# schematic.net
KiCad netlist of a schematic drawn in EAGLE
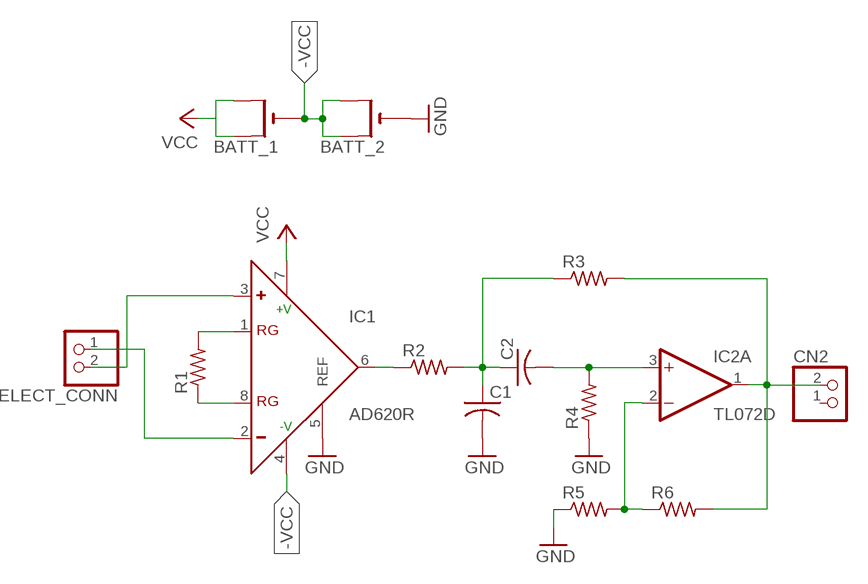
[diagram p0: schematic, sheet 1]

(export (version "E")
  (design (tool "Eeschema 10.0.6"))
  (components
    (comp (ref "BATT_1")
      (value "CR1220SMT")
      (footprint "eagle-import:CR1220-SMD")
      (libsource (lib "eagle-import") (part "CR1220SMT"))
    )
    (comp (ref "BATT_2")
      (value "CR1220SMT")
      (footprint "eagle-import:CR1220-SMD")
      (libsource (lib "eagle-import") (part "CR1220SMT"))
    )
    (comp (ref "C1")
      (value "C-USC0805")
      (footprint "eagle-import:C0805")
      (libsource (lib "eagle-import") (part "C-USC0805"))
    )
    (comp (ref "C2")
      (value "C-USC0805")
      (footprint "eagle-import:C0805")
      (libsource (lib "eagle-import") (part "C-USC0805"))
    )
    (comp (ref "CN2")
      (value "JST_2PIN-SMT-RA")
      (footprint "eagle-import:JST-PH-2-SMT-RA")
      (libsource (lib "eagle-import") (part "JST_2PIN-SMT-RA"))
    )
    (comp (ref "ELECT_CONN")
      (value "JST_2PIN-SMT-RA")
      (footprint "eagle-import:JST-PH-2-SMT-RA")
      (libsource (lib "eagle-import") (part "JST_2PIN-SMT-RA"))
    )
    (comp (ref "IC1")
      (value "AD620R")
      (footprint "eagle-import:SO8")
      (fields (field (name "MPN") "AD620AR"))
      (libsource (lib "eagle-import") (part "AD620R"))
    )
    (comp (ref "IC2")
      (value "TL072D")
      (footprint "eagle-import:SO08")
      (libsource (lib "eagle-import") (part "TL072D"))
    )
    (comp (ref "R1")
      (value "R-US_R0805")
      (footprint "eagle-import:R0805")
      (libsource (lib "eagle-import") (part "R-US_R0805"))
    )
    (comp (ref "R2")
      (value "R-US_R0805")
      (footprint "eagle-import:R0805")
      (libsource (lib "eagle-import") (part "R-US_R0805"))
    )
    (comp (ref "R3")
      (value "R-US_R0805")
      (footprint "eagle-import:R0805")
      (libsource (lib "eagle-import") (part "R-US_R0805"))
    )
    (comp (ref "R4")
      (value "R-US_R0805")
      (footprint "eagle-import:R0805")
      (libsource (lib "eagle-import") (part "R-US_R0805"))
    )
    (comp (ref "R5")
      (value "R-US_R0805")
      (footprint "eagle-import:R0805")
      (libsource (lib "eagle-import") (part "R-US_R0805"))
    )
    (comp (ref "R6")
      (value "R-US_R0805")
      (footprint "eagle-import:R0805")
      (libsource (lib "eagle-import") (part "R-US_R0805"))
    )
  )
  (nets
    (net (code "1") (name "-VCC") (class "Default")
      (node (ref "BATT_1") (pin "-") (pinfunction "-_-") (pintype "passive"))
      (node (ref "BATT_2") (pin "+$1") (pinfunction "+_+$1") (pintype "passive"))
      (node (ref "BATT_2") (pin "+$2") (pinfunction "+1_+$2") (pintype "passive"))
      (node (ref "IC1") (pin "4") (pinfunction "-V_4") (pintype "power_in"))
    )
    (net (code "2") (name "GND") (class "Default")
      (node (ref "BATT_2") (pin "-") (pinfunction "-_-") (pintype "passive"))
      (node (ref "C1") (pin "2") (pinfunction "2_2") (pintype "passive"))
      (node (ref "IC1") (pin "5") (pinfunction "REF_5") (pintype "passive"))
      (node (ref "R4") (pin "1") (pinfunction "1_1") (pintype "passive"))
      (node (ref "R5") (pin "1") (pinfunction "1_1") (pintype "passive"))
    )
    (net (code "3") (name "Net-(C1-Pad1)") (class "Default")
      (node (ref "C1") (pin "1") (pinfunction "1_1") (pintype "passive"))
      (node (ref "C2") (pin "1") (pinfunction "1_1") (pintype "passive"))
      (node (ref "R2") (pin "2") (pinfunction "2_2") (pintype "passive"))
      (node (ref "R3") (pin "1") (pinfunction "1_1") (pintype "passive"))
    )
    (net (code "4") (name "Net-(CN2-1)") (class "Default")
      (node (ref "CN2") (pin "2") (pinfunction "1_2") (pintype "passive"))
      (node (ref "IC2") (pin "1") (pinfunction "OUT_1") (pintype "output"))
      (node (ref "R3") (pin "2") (pinfunction "2_2") (pintype "passive"))
      (node (ref "R6") (pin "2") (pinfunction "2_2") (pintype "passive"))
    )
    (net (code "5") (name "Net-(ELECT_CONN-1)") (class "Default")
      (node (ref "ELECT_CONN") (pin "2") (pinfunction "1_2") (pintype "passive"))
      (node (ref "IC1") (pin "3") (pinfunction "+_3") (pintype "input"))
    )
    (net (code "6") (name "Net-(ELECT_CONN-2)") (class "Default")
      (node (ref "ELECT_CONN") (pin "1") (pinfunction "2_1") (pintype "passive"))
      (node (ref "IC1") (pin "2") (pinfunction "-_2") (pintype "input"))
    )
    (net (code "7") (name "Net-(IC1-OUT)") (class "Default")
      (node (ref "IC1") (pin "6") (pinfunction "OUT_6") (pintype "output"))
      (node (ref "R2") (pin "1") (pinfunction "1_1") (pintype "passive"))
    )
    (net (code "8") (name "Net-(IC1-RG-Pad1)") (class "Default")
      (node (ref "IC1") (pin "1") (pinfunction "RG_1") (pintype "passive"))
      (node (ref "R1") (pin "2") (pinfunction "2_2") (pintype "passive"))
    )
    (net (code "9") (name "Net-(IC1-RG-Pad8)") (class "Default")
      (node (ref "IC1") (pin "8") (pinfunction "RG_8") (pintype "passive"))
      (node (ref "R1") (pin "1") (pinfunction "1_1") (pintype "passive"))
    )
    (net (code "10") (name "Net-(IC2A-+IN)") (class "Default")
      (node (ref "C2") (pin "2") (pinfunction "2_2") (pintype "passive"))
      (node (ref "IC2") (pin "3") (pinfunction "+IN_3") (pintype "input"))
      (node (ref "R4") (pin "2") (pinfunction "2_2") (pintype "passive"))
    )
    (net (code "11") (name "Net-(IC2A--IN)") (class "Default")
      (node (ref "IC2") (pin "2") (pinfunction "-IN_2") (pintype "input"))
      (node (ref "R5") (pin "2") (pinfunction "2_2") (pintype "passive"))
      (node (ref "R6") (pin "1") (pinfunction "1_1") (pintype "passive"))
    )
    (net (code "12") (name "VCC") (class "Default")
      (node (ref "BATT_1") (pin "+$1") (pinfunction "+_+$1") (pintype "passive"))
      (node (ref "BATT_1") (pin "+$2") (pinfunction "+1_+$2") (pintype "passive"))
      (node (ref "IC1") (pin "7") (pinfunction "+V_7") (pintype "power_in"))
    )
    (net (code "13") (name "unconnected-(CN2-2-Pad1)") (class "Default")
      (node (ref "CN2") (pin "1") (pinfunction "2_1") (pintype "passive"))
    )
  )
)
